# touch-1ch-sp.net
KiCad netlist of a schematic drawn in Altium Designer
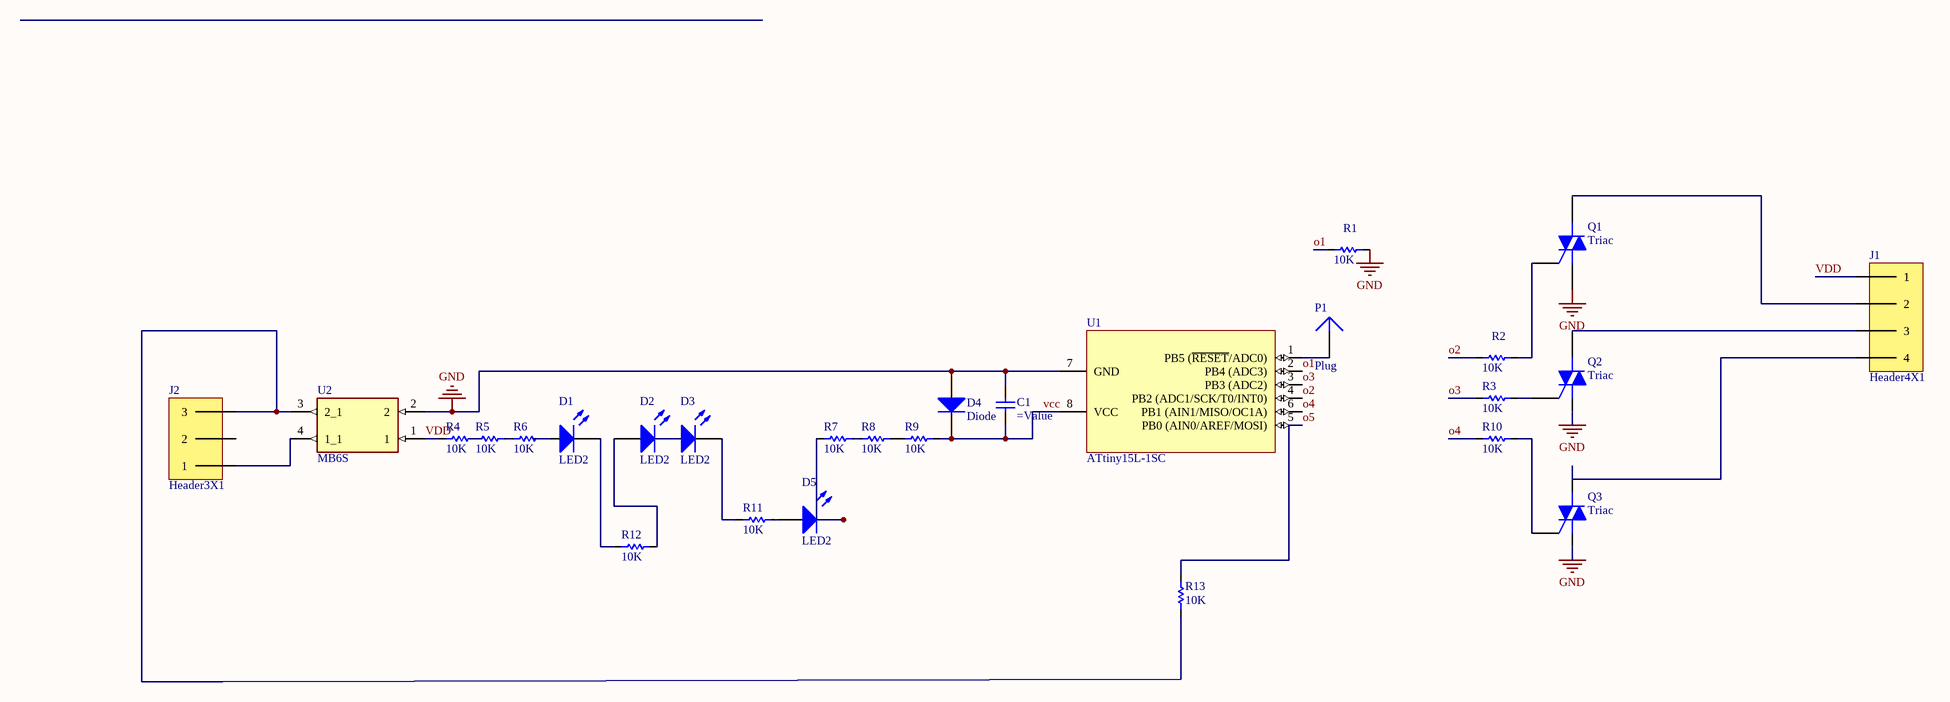
[diagram p0: touch-1ch-sp.SchDoc]

(export (version "E")
  (design (tool "Eeschema 10.0.6"))
  (components
    (comp (ref "C1")
      (value "~")
      (footprint "CAP 1206")
      (description "Capacitor")
      (libsource (lib "AltiumLib1") (part "Capacitor"))
    )
    (comp (ref "D1")
      (value "LED2")
      (footprint "3.2X1.6X1.1")
      (description "Typical RED, GREEN, YELLOW, AMBER GaAs LED")
      (fields (field (name "PUBLISHER") "Altium Limited"))
      (libsource (lib "Miscellaneous Devices") (part "LED2"))
    )
    (comp (ref "D2")
      (value "LED2")
      (footprint "3.2X1.6X1.1")
      (description "Typical RED, GREEN, YELLOW, AMBER GaAs LED")
      (fields (field (name "PUBLISHER") "Altium Limited"))
      (libsource (lib "Miscellaneous Devices") (part "LED2"))
    )
    (comp (ref "D3")
      (value "LED2")
      (footprint "3.2X1.6X1.1")
      (description "Typical RED, GREEN, YELLOW, AMBER GaAs LED")
      (fields (field (name "PUBLISHER") "Altium Limited"))
      (libsource (lib "Miscellaneous Devices") (part "LED2"))
    )
    (comp (ref "D4")
      (value "Diode")
      (footprint "C1206")
      (description "Default Diode")
      (fields (field (name "PUBLISHER") "Altium Limited"))
      (libsource (lib "Miscellaneous Devices") (part "Diode"))
    )
    (comp (ref "D5")
      (value "LED2")
      (footprint "3.2X1.6X1.1")
      (description "Typical RED, GREEN, YELLOW, AMBER GaAs LED")
      (fields (field (name "PUBLISHER") "Altium Limited"))
      (libsource (lib "Miscellaneous Devices") (part "LED2"))
    )
    (comp (ref "J1")
      (value "Header4X1")
      (footprint "HEADER 4X1")
      (libsource (lib "AltiumLib1") (part "Header4X1"))
    )
    (comp (ref "J2")
      (value "Header3X1")
      (footprint "HEADER 3X1")
      (libsource (lib "AltiumLib1") (part "Header3X1"))
    )
    (comp (ref "P1")
      (value "Plug")
      (footprint "PIN1")
      (fields (field (name "PUBLISHER") "Altium Limited"))
      (libsource (lib "Miscellaneous Connectors") (part "Plug"))
    )
    (comp (ref "Q1")
      (value "Triac")
      (footprint "SOT89N")
      (description "Silicon Bidirectional Triode Thyristor")
      (fields (field (name "PUBLISHER") "Altium Limited"))
      (libsource (lib "Miscellaneous Devices") (part "Triac"))
    )
    (comp (ref "Q2")
      (value "Triac")
      (footprint "SOT89N")
      (description "Silicon Bidirectional Triode Thyristor")
      (fields (field (name "PUBLISHER") "Altium Limited"))
      (libsource (lib "Miscellaneous Devices") (part "Triac"))
    )
    (comp (ref "Q3")
      (value "Triac")
      (footprint "SOT89N")
      (description "Silicon Bidirectional Triode Thyristor")
      (fields (field (name "PUBLISHER") "Altium Limited"))
      (libsource (lib "Miscellaneous Devices") (part "Triac"))
    )
    (comp (ref "R1")
      (value "10K")
      (footprint "RES 1206 (3216X08L)")
      (description "Resistor")
      (fields (field (name "TOLERANCE") "5%") (field (name "POWER") "1/4 W"))
      (libsource (lib "AltiumLib1") (part "Resistor"))
    )
    (comp (ref "R2")
      (value "10K")
      (footprint "RES 1206 (3216X08L)")
      (description "Resistor")
      (fields (field (name "TOLERANCE") "5%") (field (name "POWER") "1/4 W"))
      (libsource (lib "AltiumLib1") (part "Resistor"))
    )
    (comp (ref "R3")
      (value "10K")
      (footprint "RES 1206 (3216X08L)")
      (description "Resistor")
      (fields (field (name "TOLERANCE") "5%") (field (name "POWER") "1/4 W"))
      (libsource (lib "AltiumLib1") (part "Resistor"))
    )
    (comp (ref "R4")
      (value "10K")
      (footprint "RES 2010 (5026X08L)")
      (description "Resistor")
      (fields (field (name "TOLERANCE") "5%") (field (name "POWER") "1/4 W"))
      (libsource (lib "AltiumLib1") (part "Resistor"))
    )
    (comp (ref "R5")
      (value "10K")
      (footprint "RES 2010 (5026X08L)")
      (description "Resistor")
      (fields (field (name "TOLERANCE") "5%") (field (name "POWER") "1/4 W"))
      (libsource (lib "AltiumLib1") (part "Resistor"))
    )
    (comp (ref "R6")
      (value "10K")
      (footprint "RES 2010 (5026X08L)")
      (description "Resistor")
      (fields (field (name "TOLERANCE") "5%") (field (name "POWER") "1/4 W"))
      (libsource (lib "AltiumLib1") (part "Resistor"))
    )
    (comp (ref "R7")
      (value "10K")
      (footprint "RES 2010 (5026X08L)")
      (description "Resistor")
      (fields (field (name "TOLERANCE") "5%") (field (name "POWER") "1/4 W"))
      (libsource (lib "AltiumLib1") (part "Resistor"))
    )
    (comp (ref "R8")
      (value "10K")
      (footprint "RES 2010 (5026X08L)")
      (description "Resistor")
      (fields (field (name "TOLERANCE") "5%") (field (name "POWER") "1/4 W"))
      (libsource (lib "AltiumLib1") (part "Resistor"))
    )
    (comp (ref "R9")
      (value "10K")
      (footprint "RES 2010 (5026X08L)")
      (description "Resistor")
      (fields (field (name "TOLERANCE") "5%") (field (name "POWER") "1/4 W"))
      (libsource (lib "AltiumLib1") (part "Resistor"))
    )
    (comp (ref "R10")
      (value "10K")
      (footprint "RES 1206 (3216X08L)")
      (description "Resistor")
      (fields (field (name "TOLERANCE") "5%") (field (name "POWER") "1/4 W"))
      (libsource (lib "AltiumLib1") (part "Resistor"))
    )
    (comp (ref "R11")
      (value "10K")
      (footprint "RES 2010 (5026X08L)")
      (description "Resistor")
      (fields (field (name "TOLERANCE") "5%") (field (name "POWER") "1/4 W"))
      (libsource (lib "AltiumLib1") (part "Resistor"))
    )
    (comp (ref "R12")
      (value "10K")
      (footprint "RES 2010 (5026X08L)")
      (description "Resistor")
      (fields (field (name "TOLERANCE") "5%") (field (name "POWER") "1/4 W"))
      (libsource (lib "AltiumLib1") (part "Resistor"))
    )
    (comp (ref "R13")
      (value "10K")
      (footprint "RES 1206 (3216X08L)")
      (description "Resistor")
      (fields (field (name "TOLERANCE") "5%") (field (name "POWER") "1/4 W"))
      (libsource (lib "AltiumLib1") (part "Resistor"))
    )
    (comp (ref "U1")
      (value "ATtiny15L-1SC")
      (footprint "8S2_N")
      (description "8-Bit AVR Microcontroller with 1K Byte of Flash Memory")
      (fields (field (name "PUBLISHER") "Altium Limited"))
      (libsource (lib "Atmel Microcontroller 8-Bit AVR") (part "ATtiny15L-1SC"))
    )
    (comp (ref "U2")
      (value "MB6S")
      (footprint "SOIC245P670X270-4N")
      (description "Bridge Rectifier Single Phase Standard 600V Surface Mount 4-SOIC")
      (fields (field (name "MF") "ON Semiconductor") (field (name "DIGI-KEY_PART_NUMBER") "MB6SCT-ND"))
      (libsource (lib "MB6S") (part "MB6S"))
    )
  )
  (nets
    (net (code "1") (name "/VDD") (class "Default")
      (node (ref "J1") (pin "1") (pinfunction "1_1") (pintype "passive"))
      (node (ref "R4") (pin "1") (pinfunction "1_1") (pintype "passive"))
      (node (ref "U2") (pin "1") (pinfunction "1_1") (pintype "input"))
    )
    (net (code "2") (name "/o1") (class "Default")
      (node (ref "R1") (pin "1") (pinfunction "1_1") (pintype "passive"))
      (node (ref "U1") (pin "2") (pinfunction "PB4_(ADC3)_2") (pintype "bidirectional"))
    )
    (net (code "3") (name "/o2") (class "Default")
      (node (ref "R2") (pin "1") (pinfunction "1_1") (pintype "passive"))
      (node (ref "U1") (pin "4") (pinfunction "PB2_(ADC1/SCK/T0/INT0)_4") (pintype "bidirectional"))
    )
    (net (code "4") (name "/o3") (class "Default")
      (node (ref "R3") (pin "1") (pinfunction "1_1") (pintype "passive"))
      (node (ref "U1") (pin "3") (pinfunction "PB3_(ADC2)_3") (pintype "bidirectional"))
    )
    (net (code "5") (name "/o4") (class "Default")
      (node (ref "R10") (pin "1") (pinfunction "1_1") (pintype "passive"))
      (node (ref "U1") (pin "6") (pinfunction "PB1_(AIN1/MISO/OC1A)_6") (pintype "bidirectional"))
    )
    (net (code "6") (name "/o5") (class "Default")
      (node (ref "R13") (pin "2") (pinfunction "2_2") (pintype "passive"))
      (node (ref "U1") (pin "5") (pinfunction "PB0_(AIN0/AREF/MOSI)_5") (pintype "bidirectional"))
    )
    (net (code "7") (name "/vcc") (class "Default")
      (node (ref "C1") (pin "1") (pinfunction "+_1") (pintype "passive"))
      (node (ref "D4") (pin "2") (pinfunction "K_2") (pintype "passive"))
      (node (ref "R9") (pin "2") (pinfunction "2_2") (pintype "passive"))
      (node (ref "U1") (pin "8") (pinfunction "VCC_8") (pintype "power_in"))
    )
    (net (code "8") (name "GND") (class "Default")
      (node (ref "C1") (pin "2") (pinfunction "-_2") (pintype "passive"))
      (node (ref "D4") (pin "1") (pinfunction "A_1") (pintype "passive"))
      (node (ref "Q1") (pin "1") (pinfunction "M1_1") (pintype "passive"))
      (node (ref "Q2") (pin "1") (pinfunction "M1_1") (pintype "passive"))
      (node (ref "Q3") (pin "1") (pinfunction "M1_1") (pintype "passive"))
      (node (ref "R1") (pin "2") (pinfunction "2_2") (pintype "passive"))
      (node (ref "U1") (pin "7") (pinfunction "GND_7") (pintype "power_in"))
      (node (ref "U2") (pin "2") (pinfunction "2_2") (pintype "input"))
    )
    (net (code "9") (name "Net-(D1-A)") (class "Default")
      (node (ref "D1") (pin "1") (pinfunction "A_1") (pintype "passive"))
      (node (ref "R6") (pin "2") (pinfunction "2_2") (pintype "passive"))
    )
    (net (code "10") (name "Net-(D1-K)") (class "Default")
      (node (ref "D1") (pin "2") (pinfunction "K_2") (pintype "passive"))
      (node (ref "R12") (pin "1") (pinfunction "1_1") (pintype "passive"))
    )
    (net (code "11") (name "Net-(D2-A)") (class "Default")
      (node (ref "D2") (pin "1") (pinfunction "A_1") (pintype "passive"))
      (node (ref "R12") (pin "2") (pinfunction "2_2") (pintype "passive"))
    )
    (net (code "12") (name "Net-(D2-K)") (class "Default")
      (node (ref "D2") (pin "2") (pinfunction "K_2") (pintype "passive"))
      (node (ref "D3") (pin "1") (pinfunction "A_1") (pintype "passive"))
    )
    (net (code "13") (name "Net-(D3-K)") (class "Default")
      (node (ref "D3") (pin "2") (pinfunction "K_2") (pintype "passive"))
      (node (ref "R11") (pin "1") (pinfunction "1_1") (pintype "passive"))
    )
    (net (code "14") (name "Net-(D5-A)") (class "Default")
      (node (ref "D5") (pin "1") (pinfunction "A_1") (pintype "passive"))
      (node (ref "R11") (pin "2") (pinfunction "2_2") (pintype "passive"))
    )
    (net (code "15") (name "Net-(D5-K)") (class "Default")
      (node (ref "D5") (pin "2") (pinfunction "K_2") (pintype "passive"))
      (node (ref "R7") (pin "1") (pinfunction "1_1") (pintype "passive"))
    )
    (net (code "16") (name "Net-(Q1-G)") (class "Default")
      (node (ref "Q1") (pin "3") (pinfunction "G_3") (pintype "passive"))
      (node (ref "R2") (pin "2") (pinfunction "2_2") (pintype "passive"))
    )
    (net (code "17") (name "Net-(Q1-M2)") (class "Default")
      (node (ref "J1") (pin "2") (pinfunction "2_2") (pintype "passive"))
      (node (ref "Q1") (pin "2") (pinfunction "M2_2") (pintype "passive"))
    )
    (net (code "18") (name "Net-(Q2-G)") (class "Default")
      (node (ref "Q2") (pin "3") (pinfunction "G_3") (pintype "passive"))
      (node (ref "R3") (pin "2") (pinfunction "2_2") (pintype "passive"))
    )
    (net (code "19") (name "Net-(Q2-M2)") (class "Default")
      (node (ref "J1") (pin "3") (pinfunction "3_3") (pintype "passive"))
      (node (ref "Q2") (pin "2") (pinfunction "M2_2") (pintype "passive"))
    )
    (net (code "20") (name "Net-(Q3-G)") (class "Default")
      (node (ref "Q3") (pin "3") (pinfunction "G_3") (pintype "passive"))
      (node (ref "R10") (pin "2") (pinfunction "2_2") (pintype "passive"))
    )
    (net (code "21") (name "Net-(Q3-M2)") (class "Default")
      (node (ref "J1") (pin "4") (pinfunction "4_4") (pintype "passive"))
      (node (ref "Q3") (pin "2") (pinfunction "M2_2") (pintype "passive"))
    )
    (net (code "22") (name "Net-(R4-Pad2)") (class "Default")
      (node (ref "R4") (pin "2") (pinfunction "2_2") (pintype "passive"))
      (node (ref "R5") (pin "1") (pinfunction "1_1") (pintype "passive"))
    )
    (net (code "23") (name "Net-(R5-Pad2)") (class "Default")
      (node (ref "R5") (pin "2") (pinfunction "2_2") (pintype "passive"))
      (node (ref "R6") (pin "1") (pinfunction "1_1") (pintype "passive"))
    )
    (net (code "24") (name "Net-(R7-Pad2)") (class "Default")
      (node (ref "R7") (pin "2") (pinfunction "2_2") (pintype "passive"))
      (node (ref "R8") (pin "1") (pinfunction "1_1") (pintype "passive"))
    )
    (net (code "25") (name "Net-(R8-Pad2)") (class "Default")
      (node (ref "R8") (pin "2") (pinfunction "2_2") (pintype "passive"))
      (node (ref "R9") (pin "1") (pinfunction "1_1") (pintype "passive"))
    )
    (net (code "26") (name "Net-(U1-PB5_(~{RESET}{slash}ADC0))") (class "Default")
      (node (ref "P1") (pin "1") (pinfunction "1_1") (pintype "passive"))
      (node (ref "U1") (pin "1") (pinfunction "PB5_(~{RESET}/ADC0)_1") (pintype "bidirectional"))
    )
    (net (code "27") (name "Net-(U2-1_1)") (class "Default")
      (node (ref "J2") (pin "1") (pinfunction "1_1") (pintype "passive"))
      (node (ref "U2") (pin "4") (pinfunction "1_1_4") (pintype "output"))
    )
    (net (code "28") (name "Net-(U2-2_1)") (class "Default")
      (node (ref "J2") (pin "3") (pinfunction "3_3") (pintype "passive"))
      (node (ref "R13") (pin "1") (pinfunction "1_1") (pintype "passive"))
      (node (ref "U2") (pin "3") (pinfunction "2_1_3") (pintype "output"))
    )
    (net (code "29") (name "unconnected-(J2-Pad2)") (class "Default")
      (node (ref "J2") (pin "2") (pinfunction "2_2") (pintype "passive"))
    )
  )
)
